# ESP8266_InlinePSU.net
KiCad netlist of a schematic drawn in EAGLE
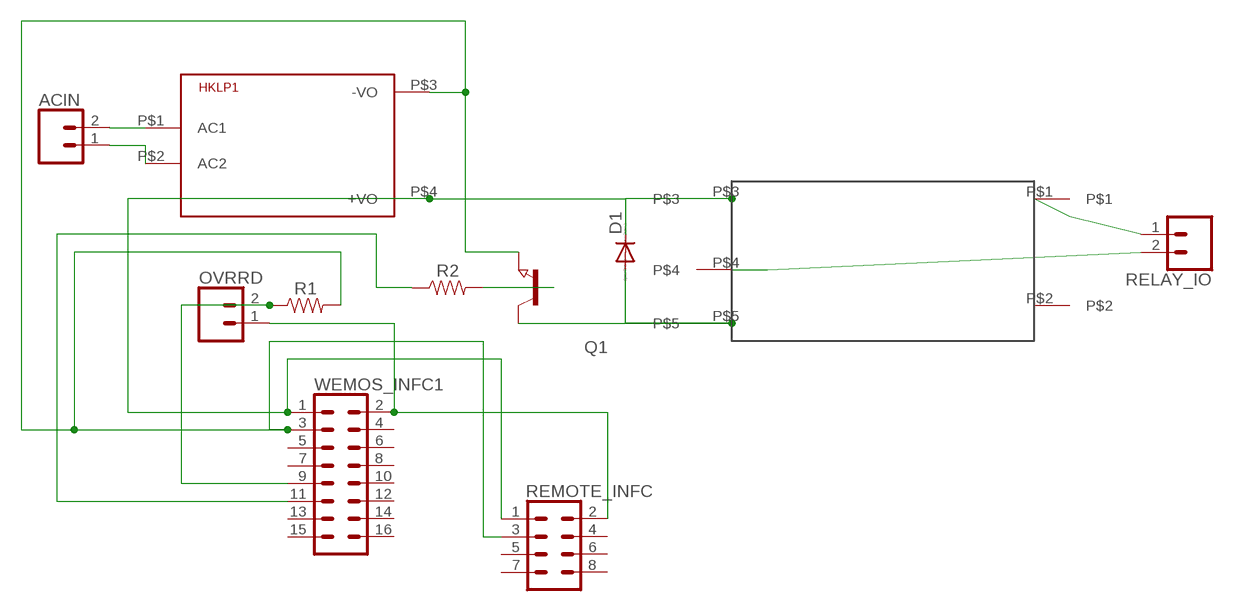
[diagram p0: schematic, sheet 1]

(export (version "E")
  (design (tool "Eeschema 10.0.6"))
  (components
    (comp (ref "ACIN")
      (value "CONN_025MM")
      (footprint "eagle-import:SCREWTERMINAL-5MM-2")
      (libsource (lib "eagle-import") (part "CONN_025MM"))
    )
    (comp (ref "D1")
      (value "1N4148DO35-7")
      (footprint "eagle-import:DO35-7")
      (libsource (lib "eagle-import") (part "1N4148DO35-7"))
    )
    (comp (ref "HKLP1")
      (value "HKLPM01")
      (footprint "eagle-import:HKLPM01")
      (libsource (lib "eagle-import") (part "HKLPM01"))
    )
    (comp (ref "OVRRD")
      (value "CONN_02LOCK")
      (footprint "eagle-import:1X02_LOCK")
      (libsource (lib "eagle-import") (part "CONN_02LOCK"))
    )
    (comp (ref "Q1")
      (value "NPN-TRANSISTOR_SOT23")
      (footprint "eagle-import:SOT23")
      (libsource (lib "eagle-import") (part "NPN-TRANSISTOR_SOT23"))
    )
    (comp (ref "R1")
      (value "RESISTOR0805")
      (footprint "eagle-import:0805")
      (libsource (lib "eagle-import") (part "RESISTOR0805"))
    )
    (comp (ref "R2")
      (value "RESISTOR0805")
      (footprint "eagle-import:0805")
      (libsource (lib "eagle-import") (part "RESISTOR0805"))
    )
    (comp (ref "RELAY_IO")
      (value "CONN_025MM")
      (footprint "eagle-import:SCREWTERMINAL-5MM-2")
      (libsource (lib "eagle-import") (part "CONN_025MM"))
    )
    (comp (ref "REMOTE_INFC")
      (value "CONN_04X2")
      (footprint "eagle-import:2X4")
      (libsource (lib "eagle-import") (part "CONN_04X2"))
    )
    (comp (ref "U$1")
      (value "SRD-05VDC-SL-CTH")
      (footprint "eagle-import:SRD-05VDC-SL-C")
      (libsource (lib "eagle-import") (part "SRD-05VDC-SL-CTH"))
    )
    (comp (ref "WEMOS_INFC1")
      (value "CONN_08X2")
      (footprint "eagle-import:2X8")
      (libsource (lib "eagle-import") (part "CONN_08X2"))
    )
  )
  (nets
    (net (code "1") (name "Net-(HKLP1-+VO)") (class "Default")
      (node (ref "D1") (pin "C") (pinfunction "C_C") (pintype "passive"))
      (node (ref "HKLP1") (pin "P$4") (pinfunction "+VO_P$4") (pintype "output"))
      (node (ref "REMOTE_INFC") (pin "1") (pinfunction "1_1") (pintype "passive"))
      (node (ref "U$1") (pin "P$3") (pinfunction "P$3_P$3") (pintype "bidirectional"))
      (node (ref "WEMOS_INFC1") (pin "1") (pinfunction "1_1") (pintype "passive"))
    )
    (net (code "2") (name "Net-(HKLP1--VO)") (class "Default")
      (node (ref "HKLP1") (pin "P$3") (pinfunction "-VO_P$3") (pintype "output"))
      (node (ref "Q1") (pin "2") (pinfunction "E_2") (pintype "passive"))
      (node (ref "R1") (pin "2") (pinfunction "2_2") (pintype "passive"))
      (node (ref "REMOTE_INFC") (pin "3") (pinfunction "3_3") (pintype "passive"))
      (node (ref "WEMOS_INFC1") (pin "3") (pinfunction "3_3") (pintype "passive"))
    )
    (net (code "3") (name "Net-(HKLP1-AC1)") (class "Default")
      (node (ref "ACIN") (pin "2") (pinfunction "2_2") (pintype "passive"))
      (node (ref "HKLP1") (pin "P$1") (pinfunction "AC1_P$1") (pintype "input"))
    )
    (net (code "4") (name "Net-(HKLP1-AC2)") (class "Default")
      (node (ref "ACIN") (pin "1") (pinfunction "1_1") (pintype "passive"))
      (node (ref "HKLP1") (pin "P$2") (pinfunction "AC2_P$2") (pintype "input"))
    )
    (net (code "5") (name "Net-(OVRRD-Pad1)") (class "Default")
      (node (ref "OVRRD") (pin "1") (pinfunction "1_1") (pintype "passive"))
      (node (ref "REMOTE_INFC") (pin "2") (pinfunction "2_2") (pintype "passive"))
      (node (ref "WEMOS_INFC1") (pin "2") (pinfunction "2_2") (pintype "passive"))
    )
    (net (code "6") (name "Net-(OVRRD-Pad2)") (class "Default")
      (node (ref "OVRRD") (pin "2") (pinfunction "2_2") (pintype "passive"))
      (node (ref "R1") (pin "1") (pinfunction "1_1") (pintype "passive"))
      (node (ref "WEMOS_INFC1") (pin "9") (pinfunction "9_9") (pintype "passive"))
    )
    (net (code "7") (name "Net-(Q1-B)") (class "Default")
      (node (ref "Q1") (pin "1") (pinfunction "B_1") (pintype "passive"))
      (node (ref "R2") (pin "2") (pinfunction "2_2") (pintype "passive"))
    )
    (net (code "8") (name "Net-(Q1-C)") (class "Default")
      (node (ref "D1") (pin "A") (pinfunction "A_A") (pintype "passive"))
      (node (ref "Q1") (pin "3") (pinfunction "C_3") (pintype "passive"))
      (node (ref "U$1") (pin "P$5") (pinfunction "P$5_P$5") (pintype "bidirectional"))
    )
    (net (code "9") (name "Net-(R2-Pad1)") (class "Default")
      (node (ref "R2") (pin "1") (pinfunction "1_1") (pintype "passive"))
      (node (ref "WEMOS_INFC1") (pin "11") (pinfunction "11_11") (pintype "passive"))
    )
    (net (code "10") (name "Net-(RELAY_IO-Pad1)") (class "Default")
      (node (ref "RELAY_IO") (pin "1") (pinfunction "1_1") (pintype "passive"))
      (node (ref "U$1") (pin "P$1") (pinfunction "P$1_P$1") (pintype "bidirectional"))
    )
    (net (code "11") (name "Net-(RELAY_IO-Pad2)") (class "Default")
      (node (ref "RELAY_IO") (pin "2") (pinfunction "2_2") (pintype "passive"))
      (node (ref "U$1") (pin "P$4") (pinfunction "P$4_P$4") (pintype "bidirectional"))
    )
    (net (code "12") (name "unconnected-(REMOTE_INFC-Pad4)") (class "Default")
      (node (ref "REMOTE_INFC") (pin "4") (pinfunction "4_4") (pintype "passive"))
    )
    (net (code "13") (name "unconnected-(REMOTE_INFC-Pad5)") (class "Default")
      (node (ref "REMOTE_INFC") (pin "5") (pinfunction "5_5") (pintype "passive"))
    )
    (net (code "14") (name "unconnected-(REMOTE_INFC-Pad6)") (class "Default")
      (node (ref "REMOTE_INFC") (pin "6") (pinfunction "6_6") (pintype "passive"))
    )
    (net (code "15") (name "unconnected-(REMOTE_INFC-Pad7)") (class "Default")
      (node (ref "REMOTE_INFC") (pin "7") (pinfunction "7_7") (pintype "passive"))
    )
    (net (code "16") (name "unconnected-(REMOTE_INFC-Pad8)") (class "Default")
      (node (ref "REMOTE_INFC") (pin "8") (pinfunction "8_8") (pintype "passive"))
    )
    (net (code "17") (name "unconnected-(U$1-PadP$2)") (class "Default")
      (node (ref "U$1") (pin "P$2") (pinfunction "P$2_P$2") (pintype "bidirectional"))
    )
    (net (code "18") (name "unconnected-(WEMOS_INFC1-Pad4)") (class "Default")
      (node (ref "WEMOS_INFC1") (pin "4") (pinfunction "4_4") (pintype "passive"))
    )
    (net (code "19") (name "unconnected-(WEMOS_INFC1-Pad5)") (class "Default")
      (node (ref "WEMOS_INFC1") (pin "5") (pinfunction "5_5") (pintype "passive"))
    )
    (net (code "20") (name "unconnected-(WEMOS_INFC1-Pad6)") (class "Default")
      (node (ref "WEMOS_INFC1") (pin "6") (pinfunction "6_6") (pintype "passive"))
    )
    (net (code "21") (name "unconnected-(WEMOS_INFC1-Pad7)") (class "Default")
      (node (ref "WEMOS_INFC1") (pin "7") (pinfunction "7_7") (pintype "passive"))
    )
    (net (code "22") (name "unconnected-(WEMOS_INFC1-Pad8)") (class "Default")
      (node (ref "WEMOS_INFC1") (pin "8") (pinfunction "8_8") (pintype "passive"))
    )
    (net (code "23") (name "unconnected-(WEMOS_INFC1-Pad10)") (class "Default")
      (node (ref "WEMOS_INFC1") (pin "10") (pinfunction "10_10") (pintype "passive"))
    )
    (net (code "24") (name "unconnected-(WEMOS_INFC1-Pad12)") (class "Default")
      (node (ref "WEMOS_INFC1") (pin "12") (pinfunction "12_12") (pintype "passive"))
    )
    (net (code "25") (name "unconnected-(WEMOS_INFC1-Pad13)") (class "Default")
      (node (ref "WEMOS_INFC1") (pin "13") (pinfunction "13_13") (pintype "passive"))
    )
    (net (code "26") (name "unconnected-(WEMOS_INFC1-Pad14)") (class "Default")
      (node (ref "WEMOS_INFC1") (pin "14") (pinfunction "14_14") (pintype "passive"))
    )
    (net (code "27") (name "unconnected-(WEMOS_INFC1-Pad15)") (class "Default")
      (node (ref "WEMOS_INFC1") (pin "15") (pinfunction "15_15") (pintype "passive"))
    )
    (net (code "28") (name "unconnected-(WEMOS_INFC1-Pad16)") (class "Default")
      (node (ref "WEMOS_INFC1") (pin "16") (pinfunction "16_16") (pintype "passive"))
    )
  )
)
